# LED.net
KiCad netlist of a schematic drawn in Altium Designer
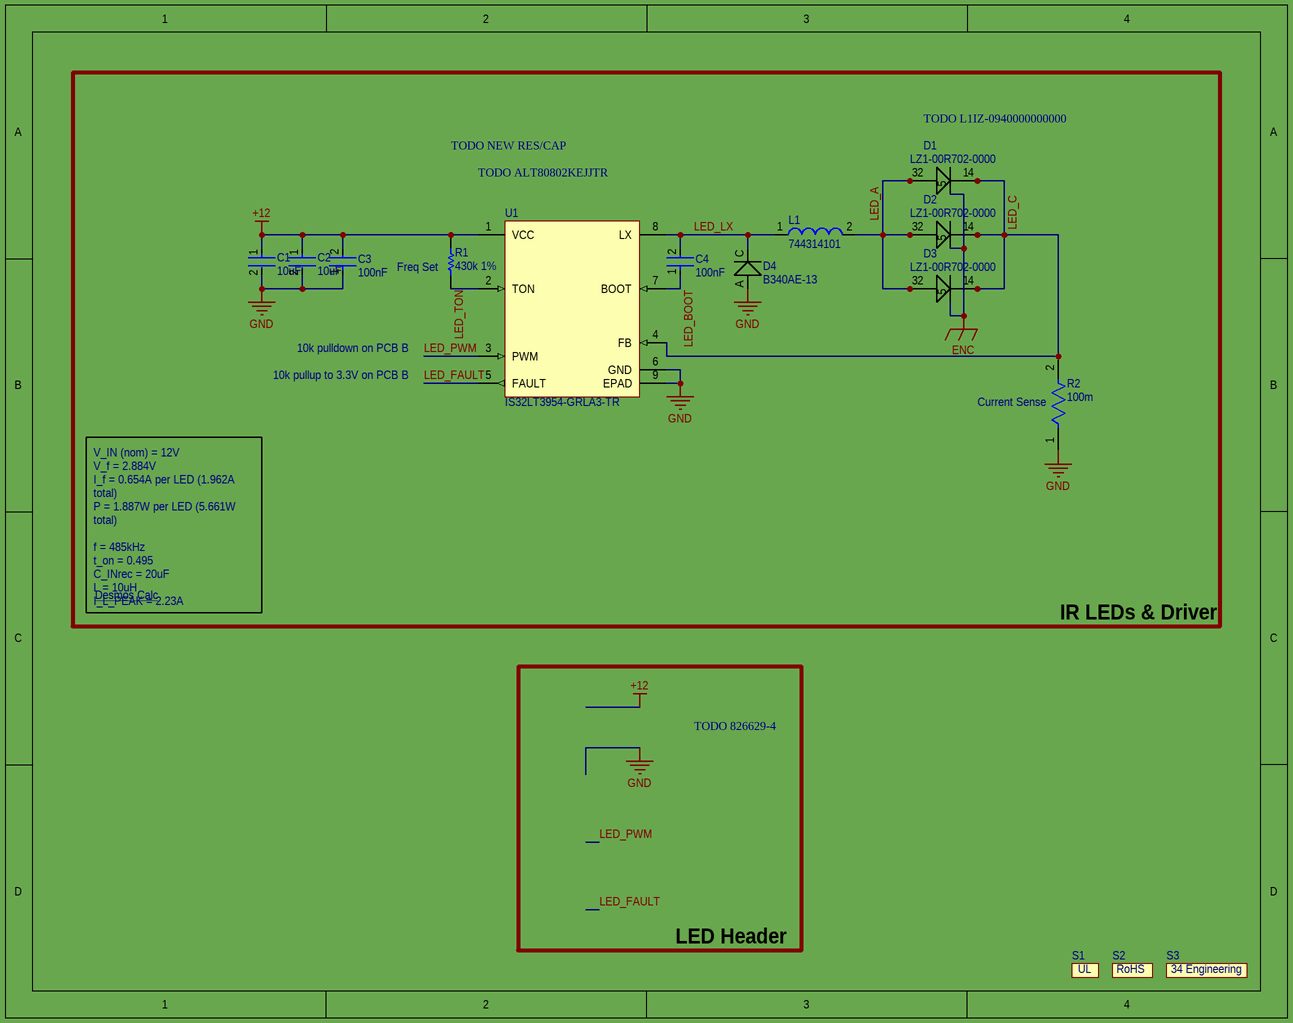
[diagram p0: LED.SchDoc]

(export (version "E")
  (design (tool "Eeschema 10.0.6"))
  (components
    (comp (ref "C1")
      (value "10uF")
      (footprint "FP-GRM188-0_2-MFG")
      (description "Chip Multilayer Ceramic Capacitors for General Purpose, 0603, 10uF, X5R, 15%, 20%, 25V")
      (fields (field (name "TOLERANCE") "20%") (field (name "VOLTAGE") "25V"))
      (libsource (lib "Altium Content Vault") (part "11868f565c42a9108669ba33697ecf6"))
    )
    (comp (ref "C2")
      (value "10uF")
      (footprint "FP-GRM188-0_2-MFG")
      (description "Chip Multilayer Ceramic Capacitors for General Purpose, 0603, 10uF, X5R, 15%, 20%, 25V")
      (fields (field (name "TOLERANCE") "20%") (field (name "VOLTAGE") "25V"))
      (libsource (lib "Altium Content Vault") (part "11868f565c42a9108669ba33697ecf6"))
    )
    (comp (ref "C3")
      (value "100nF")
      (footprint "FP-CGA3E-0_3-0_1-IPC_C")
      (description "Cap Ceramic 100nF 50V X7R 10% Pad SMD 0603 +125°C Automotive T/R")
      (fields (field (name "TOLERANCE") "10%") (field (name "VOLTAGE") "50V"))
      (libsource (lib "Altium Content Vault") (part "b4654b650e69147ec39a6b967a45e02"))
    )
    (comp (ref "C4")
      (value "100nF")
      (footprint "FP-CGA3E-0_3-0_1-IPC_C")
      (description "Cap Ceramic 100nF 50V X7R 10% Pad SMD 0603 +125°C Automotive T/R")
      (fields (field (name "TOLERANCE") "10%") (field (name "VOLTAGE") "50V"))
      (libsource (lib "Altium Content Vault") (part "b4654b650e69147ec39a6b967a45e02"))
    )
    (comp (ref "D1")
      (value "LZ1-00R702-0000")
      (footprint "LZ1-00R702-0000")
      (description "IR Emitter 940nm 1600mW 1200mA 3.05V 4-Pin CSMD T/R")
      (fields (field (name "MANUFACTURER") "LED Engin"))
      (libsource (lib "Virtex") (part "LZ1-00R702-0000"))
    )
    (comp (ref "D2")
      (value "LZ1-00R702-0000")
      (footprint "LZ1-00R702-0000")
      (description "IR Emitter 940nm 1600mW 1200mA 3.05V 4-Pin CSMD T/R")
      (fields (field (name "MANUFACTURER") "LED Engin"))
      (libsource (lib "Virtex") (part "LZ1-00R702-0000"))
    )
    (comp (ref "D3")
      (value "LZ1-00R702-0000")
      (footprint "LZ1-00R702-0000")
      (description "IR Emitter 940nm 1600mW 1200mA 3.05V 4-Pin CSMD T/R")
      (fields (field (name "MANUFACTURER") "LED Engin"))
      (libsource (lib "Virtex") (part "LZ1-00R702-0000"))
    )
    (comp (ref "D4")
      (value "B340AE-13")
      (footprint "B340AE-13")
      (description "Rectifier Diode Schottky 40V 3A 2-Pin SMA T/R")
      (fields (field (name "MANUFACTURER") "Diodes"))
      (libsource (lib "Virtex") (part "B340AE-13"))
    )
    (comp (ref "L1")
      (value "744314101")
      (footprint "WE-HCI-7050")
      (description "SMD Flat Wire High Current Inductor WE-HCI, L=10.0 µH")
      (libsource (lib "Altium Content Vault") (part "PAS-IND-INDUCTOR-2"))
    )
    (comp (ref "R1")
      (value "430k 1%")
      (footprint "RESC1608X55X30LL15T15")
      (fields (field (name "MANUFACTURER") "Panasonic") (field (name "PART NUMBER") "ERJ-3EKF4303V"))
      (libsource (lib "Altium Content Vault") (part "RES"))
    )
    (comp (ref "R2")
      (value "100m")
      (footprint "FP-ERJ6D-MFG")
      (description "RES 0.1 OHM 1% 1/2W 0805")
      (fields (field (name "TOLERANCE") "1%"))
      (libsource (lib "Altium Content Vault") (part "1029c3af85768c4190bb7ad29bc67b5"))
    )
    (comp (ref "S1") (value "~") (footprint "UL") (libsource (lib "Virtex") (part "UL")))
    (comp (ref "S2") (value "~") (footprint "RoHS") (libsource (lib "Virtex") (part "RoHS")))
    (comp (ref "S3")
      (value "~")
      (footprint "34EngineeringLogo")
      (description "34 Engineering Silkscreen Logo")
      (libsource (lib "Virtex") (part "34EngineeringLogo"))
    )
    (comp (ref "U1")
      (value "IS32LT3954-GRLA3-TR")
      (footprint "IS32LT3954-GRLA3-TR")
      (description "3.0A Dimmable Buck Switching Regulator with Fault Reporting, Spread Spectrum, SOP-8-EP")
      (fields (field (name "MANUFACTURER") "ISSI"))
      (libsource (lib "Virtex") (part "IS32LT3954-GRLA3-TR"))
    )
  )
  (nets
    (net (code "1") (name "+12") (class "Default")
      (node (ref "C1") (pin "1") (pinfunction "1_1") (pintype "passive"))
      (node (ref "C2") (pin "1") (pinfunction "1_1") (pintype "passive"))
      (node (ref "C3") (pin "2") (pinfunction "2_2") (pintype "passive"))
      (node (ref "R1") (pin "2") (pinfunction "2_2") (pintype "passive"))
      (node (ref "U1") (pin "1") (pinfunction "VCC_1") (pintype "power_in"))
    )
    (net (code "2") (name "/LED_A") (class "Default")
      (node (ref "D1") (pin "2") (pintype "power_in"))
      (node (ref "D1") (pin "3") (pintype "power_in"))
      (node (ref "D2") (pin "2") (pintype "power_in"))
      (node (ref "D2") (pin "3") (pintype "power_in"))
      (node (ref "D3") (pin "2") (pintype "power_in"))
      (node (ref "D3") (pin "3") (pintype "power_in"))
      (node (ref "L1") (pin "2") (pinfunction "2_2") (pintype "passive"))
    )
    (net (code "3") (name "/LED_BOOT") (class "Default")
      (node (ref "C4") (pin "1") (pinfunction "1_1") (pintype "passive"))
      (node (ref "U1") (pin "7") (pinfunction "BOOT_7") (pintype "input"))
    )
    (net (code "4") (name "/LED_C") (class "Default")
      (node (ref "D1") (pin "1") (pintype "power_in"))
      (node (ref "D1") (pin "4") (pintype "power_in"))
      (node (ref "D2") (pin "1") (pintype "power_in"))
      (node (ref "D2") (pin "4") (pintype "power_in"))
      (node (ref "D3") (pin "1") (pintype "power_in"))
      (node (ref "D3") (pin "4") (pintype "power_in"))
      (node (ref "R2") (pin "2") (pinfunction "2_2") (pintype "passive"))
      (node (ref "U1") (pin "4") (pinfunction "FB_4") (pintype "input"))
    )
    (net (code "5") (name "/LED_FAULT") (class "Default")
      (node (ref "U1") (pin "5") (pinfunction "FAULT_5") (pintype "output"))
    )
    (net (code "6") (name "/LED_LX") (class "Default")
      (node (ref "C4") (pin "2") (pinfunction "2_2") (pintype "passive"))
      (node (ref "D4") (pin "C") (pintype "power_in"))
      (node (ref "L1") (pin "1") (pinfunction "1_1") (pintype "passive"))
      (node (ref "U1") (pin "8") (pinfunction "LX_8") (pintype "power_in"))
    )
    (net (code "7") (name "/LED_PWM") (class "Default")
      (node (ref "U1") (pin "3") (pinfunction "PWM_3") (pintype "input"))
    )
    (net (code "8") (name "/LED_TON") (class "Default")
      (node (ref "R1") (pin "1") (pinfunction "1_1") (pintype "passive"))
      (node (ref "U1") (pin "2") (pinfunction "TON_2") (pintype "input"))
    )
    (net (code "9") (name "ENC") (class "Default")
      (node (ref "D1") (pin "5") (pintype "power_in"))
      (node (ref "D2") (pin "5") (pintype "power_in"))
      (node (ref "D3") (pin "5") (pintype "power_in"))
    )
    (net (code "10") (name "GND") (class "Default")
      (node (ref "C1") (pin "2") (pinfunction "2_2") (pintype "passive"))
      (node (ref "C2") (pin "2") (pinfunction "2_2") (pintype "passive"))
      (node (ref "C3") (pin "1") (pinfunction "1_1") (pintype "passive"))
      (node (ref "D4") (pin "A") (pintype "power_in"))
      (node (ref "R2") (pin "1") (pinfunction "1_1") (pintype "passive"))
      (node (ref "U1") (pin "6") (pinfunction "GND_6") (pintype "power_in"))
      (node (ref "U1") (pin "9") (pinfunction "EPAD_9") (pintype "power_in"))
    )
  )
)
